# Controller.net
KiCad netlist of a schematic drawn in Altium Designer
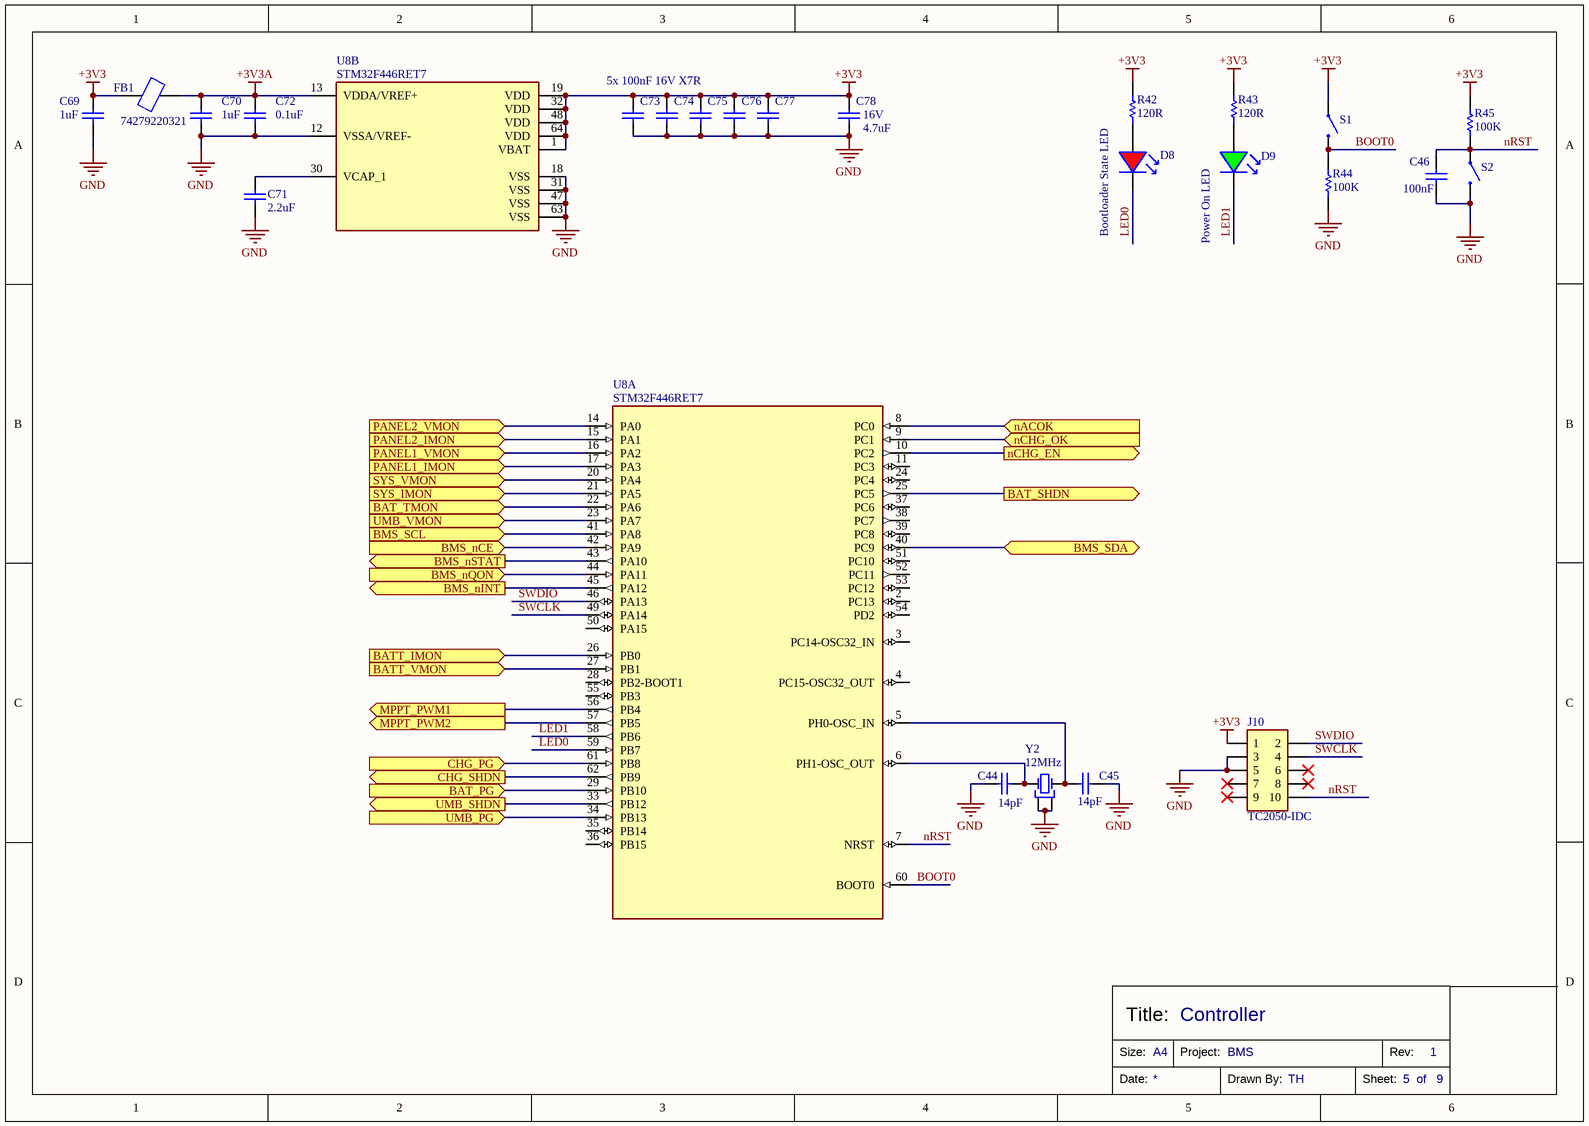
[diagram p0: Controller.SchDoc]

(export (version "E")
  (design (tool "Eeschema 10.0.6"))
  (components
    (comp (ref "C44")
      (value "GJM1555C1H140FB01D")
      (footprint "CAPC0402X020")
      (description "14 pF ±1% 50V Ceramic Capacitor C0G, NP0 0402 (1005 Metric)")
      (fields
        (field (name "TOLERANCE") "1%")
        (field (name "DISTRIBUTOR PART NUMBER") "2266-GJM1555C1H140FB01DTR-ND")
        (field (name "CAPACITANCE") "14pF")
      )
      (libsource (lib "Ahristi_Library") (part "CAPC0402"))
    )
    (comp (ref "C45")
      (value "GJM1555C1H140FB01D")
      (footprint "CAPC0402X020")
      (description "14 pF ±1% 50V Ceramic Capacitor C0G, NP0 0402 (1005 Metric)")
      (fields
        (field (name "TOLERANCE") "1%")
        (field (name "DISTRIBUTOR PART NUMBER") "2266-GJM1555C1H140FB01DTR-ND")
        (field (name "CAPACITANCE") "14pF")
      )
      (libsource (lib "Ahristi_Library") (part "CAPC0402"))
    )
    (comp (ref "C46")
      (value "CL10B104KO8NNNC")
      (footprint "CAPC0603X040")
      (description "0.1 µF ±10% 16V Ceramic Capacitor X7R 0603 (1608 Metric)")
      (fields
        (field (name "TOLERANCE") "10%")
        (field (name "DISTRIBUTOR PART NUMBER") "1276-1005-1-ND")
        (field (name "CAPACITANCE") "100nF")
      )
      (libsource (lib "Ahristi_Library") (part "CAPC0603"))
    )
    (comp (ref "C69")
      (value "CL10B105KO8NNNC")
      (footprint "CAPC0603X040")
      (description "1 µF ±10% 16V Ceramic Capacitor X7R 0603 (1608 Metric)")
      (fields
        (field (name "TOLERANCE") "10%")
        (field (name "DISTRIBUTOR PART NUMBER") "1276-1019-1-ND")
        (field (name "CAPACITANCE") "1uF")
      )
      (libsource (lib "Ahristi_Library") (part "CAPC0603"))
    )
    (comp (ref "C70")
      (value "CL10B105KO8NNNC")
      (footprint "CAPC0603X040")
      (description "1 µF ±10% 16V Ceramic Capacitor X7R 0603 (1608 Metric)")
      (fields
        (field (name "TOLERANCE") "10%")
        (field (name "DISTRIBUTOR PART NUMBER") "1276-1019-1-ND")
        (field (name "CAPACITANCE") "1uF")
      )
      (libsource (lib "Ahristi_Library") (part "CAPC0603"))
    )
    (comp (ref "C71")
      (value "CL21A225KBFNNNE")
      (footprint "CAPC0805X060")
      (description "2.2uF ±10% 25V Ceramic Capacitor X7R 0805 (2012 Metric)")
      (fields
        (field (name "DISTRIBUTOR PART NUMBER") "1276-6702-1-ND")
        (field (name "TOLERANCE") "10%")
        (field (name "CAPACITANCE") "2.2uF")
      )
      (libsource (lib "Ahristi_Library") (part "CL21A225KBFNNNE"))
    )
    (comp (ref "C72")
      (value "CL05B104KB5NNNC")
      (footprint "CAPC0402X020")
      (description "0.1 µF ±10% 50V Ceramic Capacitor X7R 0402 (1005 Metric)")
      (fields
        (field (name "TOLERANCE") "10%")
        (field (name "DISTRIBUTOR PART NUMBER") "1276-CL05B104KB5NNNCCT-ND")
        (field (name "CAPACITANCE") "0.1uF")
      )
      (libsource (lib "Ahristi_Library") (part "CL05B104KB5NNNC"))
    )
    (comp (ref "C73")
      (value "CL05B104KB5NNNC")
      (footprint "CAPC0402X020")
      (description "0.1 µF ±10% 50V Ceramic Capacitor X7R 0402 (1005 Metric)")
      (fields
        (field (name "TOLERANCE") "10%")
        (field (name "DISTRIBUTOR PART NUMBER") "1276-CL05B104KB5NNNCCT-ND")
      )
      (libsource (lib "Ahristi_Library") (part "CL05B104KB5NNNC"))
    )
    (comp (ref "C74")
      (value "CL05B104KB5NNNC")
      (footprint "CAPC0402X020")
      (description "0.1 µF ±10% 50V Ceramic Capacitor X7R 0402 (1005 Metric)")
      (fields
        (field (name "TOLERANCE") "10%")
        (field (name "DISTRIBUTOR PART NUMBER") "1276-CL05B104KB5NNNCCT-ND")
      )
      (libsource (lib "Ahristi_Library") (part "CL05B104KB5NNNC"))
    )
    (comp (ref "C75")
      (value "CL05B104KB5NNNC")
      (footprint "CAPC0402X020")
      (description "0.1 µF ±10% 50V Ceramic Capacitor X7R 0402 (1005 Metric)")
      (fields
        (field (name "TOLERANCE") "10%")
        (field (name "DISTRIBUTOR PART NUMBER") "1276-CL05B104KB5NNNCCT-ND")
      )
      (libsource (lib "Ahristi_Library") (part "CL05B104KB5NNNC"))
    )
    (comp (ref "C76")
      (value "CL05B104KB5NNNC")
      (footprint "CAPC0402X020")
      (description "0.1 µF ±10% 50V Ceramic Capacitor X7R 0402 (1005 Metric)")
      (fields
        (field (name "TOLERANCE") "10%")
        (field (name "DISTRIBUTOR PART NUMBER") "1276-CL05B104KB5NNNCCT-ND")
      )
      (libsource (lib "Ahristi_Library") (part "CL05B104KB5NNNC"))
    )
    (comp (ref "C77")
      (value "CL05B104KB5NNNC")
      (footprint "CAPC0402X020")
      (description "0.1 µF ±10% 50V Ceramic Capacitor X7R 0402 (1005 Metric)")
      (fields
        (field (name "TOLERANCE") "10%")
        (field (name "DISTRIBUTOR PART NUMBER") "1276-CL05B104KB5NNNCCT-ND")
      )
      (libsource (lib "Ahristi_Library") (part "CL05B104KB5NNNC"))
    )
    (comp (ref "C78")
      (value "CL21B475KOFNFNE")
      (footprint "CAPC0805X060")
      (description "4.7 µF ±10% 16V Ceramic Capacitor X7R 0805 (2012 Metric)")
      (fields
        (field (name "DISTRIBUTOR PART NUMBER") "1276-2970-1-ND")
        (field (name "TOLERANCE") "10%")
        (field (name "VOLTAGE RATING") "16V")
        (field (name "CAPACITANCE") "4.7uF")
      )
      (libsource (lib "Ahristi_Library") (part "CL21B475KOFNFNE"))
    )
    (comp (ref "D8")
      (value "LTST-C170EKT")
      (footprint "LEDR_0805")
      (description "Red 621nm LED Indication - Discrete 2V 0805 (2012 Metric)")
      (fields (field (name "DISTRIBUTOR PART NUMBER") "160-1178-1-ND"))
      (libsource (lib "Ahristi_Library") (part "LEDR0805"))
    )
    (comp (ref "D9")
      (value "LTST-C170GKT")
      (footprint "LEDG_0805")
      (description "Green 569nm LED Indication - Discrete 2.1V 0805 (2012 Metric)")
      (fields (field (name "DISTRIBUTOR PART NUMBER") "160-1179-1-ND"))
      (libsource (lib "Ahristi_Library") (part "LEDG0805"))
    )
    (comp (ref "FB1")
      (value "74279220321")
      (footprint "74279220321")
      (description "Ferrite Bead 320 Ohms @ 100 MHz 1 Ferrite Bead 0805 (2012 Metric) 2.5A 50mOhm")
      (fields (field (name "DISTRIBUTOR PART NUMBER") "732-6125-1-ND"))
      (libsource (lib "Ahristi_Library") (part "74279220321"))
    )
    (comp (ref "J10")
      (value "TC2050-IDC")
      (footprint "TC2050-IDC")
      (description "JTAG Pogo Programmer Pads")
      (libsource (lib "Ahristi_Library") (part "TC2050-IDC"))
    )
    (comp (ref "R42")
      (value "RMCF0805FT120R")
      (footprint "RESC0805")
      (description "120 Ohms ±1% 0.125W, 1/8W Chip Resistor 0805 (2012 Metric) Automotive AEC-Q200 Thick Film")
      (fields
        (field (name "TOLERANCE") "1%")
        (field (name "DISTRIBUTOR PART NUMBER") "738-RMCF0805FT120RCT-ND")
        (field (name "RESISTANCE") "120R")
      )
      (libsource (lib "Ahristi_Library") (part "RMCF0805FT120R"))
    )
    (comp (ref "R43")
      (value "RMCF0805FT120R")
      (footprint "RESC0805")
      (description "120 Ohms ±1% 0.125W, 1/8W Chip Resistor 0805 (2012 Metric) Automotive AEC-Q200 Thick Film")
      (fields
        (field (name "TOLERANCE") "1%")
        (field (name "DISTRIBUTOR PART NUMBER") "738-RMCF0805FT120RCT-ND")
        (field (name "RESISTANCE") "120R")
      )
      (libsource (lib "Ahristi_Library") (part "RMCF0805FT120R"))
    )
    (comp (ref "R44")
      (value "RMCF0603FT100K")
      (footprint "RESC0603")
      (description "100 kOhms ±1% 0.1W, 1/10W Chip Resistor 0603 (1608 Metric) Automotive AEC-Q200 Thick Film")
      (fields
        (field (name "TOLERANCE") "1%")
        (field (name "DISTRIBUTOR PART NUMBER") "RMCF0603FT100KCT-ND")
        (field (name "RESISTANCE") "100K")
      )
      (libsource (lib "Ahristi_Library") (part "RMCF0603FT100K"))
    )
    (comp (ref "R45")
      (value "RMCF0603FT100K")
      (footprint "RESC0603")
      (description "100 kOhms ±1% 0.1W, 1/10W Chip Resistor 0603 (1608 Metric) Automotive AEC-Q200 Thick Film")
      (fields
        (field (name "TOLERANCE") "1%")
        (field (name "DISTRIBUTOR PART NUMBER") "RMCF0603FT100KCT-ND")
        (field (name "RESISTANCE") "100K")
      )
      (libsource (lib "Ahristi_Library") (part "RMCF0603FT100K"))
    )
    (comp (ref "S1")
      (value "B3U-1000P")
      (footprint "B3U-1000P")
      (description "Tactile Switch SPST-NO Top Actuated Surface Mount")
      (fields (field (name "DISTRIBUTOR PART NUMBER") "SW1020CT-ND"))
      (libsource (lib "Ahristi_Library") (part "B3U-1000P"))
    )
    (comp (ref "S2")
      (value "B3U-1000P")
      (footprint "B3U-1000P")
      (description "Tactile Switch SPST-NO Top Actuated Surface Mount")
      (fields (field (name "DISTRIBUTOR PART NUMBER") "SW1020CT-ND"))
      (libsource (lib "Ahristi_Library") (part "B3U-1000P"))
    )
    (comp (ref "U8")
      (value "STM32F446RET7")
      (footprint "LQFP-64")
      (description "ARM® Cortex®-M4 STM32F4 Microcontroller IC 32-Bit 180MHz 512KB (512K x 8) FLASH 64-LQFP (10x10)")
      (fields
        (field (name "PART NUMBER") "STM32F446RET6")
        (field (name "DISTRIBUTOR PART NUMBER") "511-STM32F446RET7")
      )
      (libsource (lib "Ahristi_Library") (part "STM32F446RET7"))
    )
    (comp (ref "Y2")
      (value "830069882")
      (footprint "830069882")
      (description "Crystals 12.0 MHZ 18PF 20PPM 120OHM")
      (fields (field (name "FREQUENCY") "12MHz"))
      (libsource (lib "Ahristi_Library") (part "830069882"))
    )
  )
  (nets
    (net (code "1") (name "+3V3") (class "Default")
      (node (ref "C69") (pin "2") (pinfunction "2_2") (pintype "passive"))
      (node (ref "C73") (pin "2") (pinfunction "2_2") (pintype "passive"))
      (node (ref "C74") (pin "2") (pinfunction "2_2") (pintype "passive"))
      (node (ref "C75") (pin "2") (pinfunction "2_2") (pintype "passive"))
      (node (ref "C76") (pin "2") (pinfunction "2_2") (pintype "passive"))
      (node (ref "C77") (pin "2") (pinfunction "2_2") (pintype "passive"))
      (node (ref "C78") (pin "2") (pinfunction "2_2") (pintype "passive"))
      (node (ref "FB1") (pin "1") (pinfunction "1_1") (pintype "passive"))
      (node (ref "J10") (pin "1") (pinfunction "1_1") (pintype "passive"))
      (node (ref "R42") (pin "2") (pinfunction "2_2") (pintype "passive"))
      (node (ref "R43") (pin "2") (pinfunction "2_2") (pintype "passive"))
      (node (ref "R45") (pin "2") (pinfunction "2_2") (pintype "passive"))
      (node (ref "S1") (pin "1") (pinfunction "1_1") (pintype "passive"))
      (node (ref "U8") (pin "1") (pinfunction "VBAT_1") (pintype "power_in"))
      (node (ref "U8") (pin "19") (pinfunction "VDD_19") (pintype "power_in"))
      (node (ref "U8") (pin "32") (pinfunction "VDD_32") (pintype "power_in"))
      (node (ref "U8") (pin "48") (pinfunction "VDD_48") (pintype "power_in"))
      (node (ref "U8") (pin "64") (pinfunction "VDD_64") (pintype "power_in"))
    )
    (net (code "2") (name "+3V3A") (class "Default")
      (node (ref "C70") (pin "2") (pinfunction "2_2") (pintype "passive"))
      (node (ref "C72") (pin "2") (pinfunction "2_2") (pintype "passive"))
      (node (ref "FB1") (pin "2") (pinfunction "2_2") (pintype "passive"))
      (node (ref "U8") (pin "13") (pinfunction "VDDA/VREF+_13") (pintype "power_in"))
    )
    (net (code "3") (name "/BATT_IMON") (class "Default")
      (node (ref "U8") (pin "26") (pinfunction "PB0_26") (pintype "bidirectional"))
    )
    (net (code "4") (name "/BATT_VMON") (class "Default")
      (node (ref "U8") (pin "27") (pinfunction "PB1_27") (pintype "bidirectional"))
    )
    (net (code "5") (name "/BAT_PG") (class "Default")
      (node (ref "U8") (pin "29") (pinfunction "PB10_29") (pintype "bidirectional"))
    )
    (net (code "6") (name "/BAT_SHDN") (class "Default")
      (node (ref "U8") (pin "25") (pinfunction "PC5_25") (pintype "bidirectional"))
    )
    (net (code "7") (name "/BAT_TMON") (class "Default")
      (node (ref "U8") (pin "22") (pinfunction "PA6_22") (pintype "bidirectional"))
    )
    (net (code "8") (name "/BMS_SCL") (class "Default")
      (node (ref "U8") (pin "41") (pinfunction "PA8_41") (pintype "bidirectional"))
    )
    (net (code "9") (name "/BMS_SDA") (class "Default")
      (node (ref "U8") (pin "40") (pinfunction "PC9_40") (pintype "bidirectional"))
    )
    (net (code "10") (name "/BMS_nCE") (class "Default")
      (node (ref "U8") (pin "42") (pinfunction "PA9_42") (pintype "bidirectional"))
    )
    (net (code "11") (name "/BMS_nINT") (class "Default")
      (node (ref "U8") (pin "45") (pinfunction "PA12_45") (pintype "bidirectional"))
    )
    (net (code "12") (name "/BMS_nQON") (class "Default")
      (node (ref "U8") (pin "44") (pinfunction "PA11_44") (pintype "bidirectional"))
    )
    (net (code "13") (name "/BMS_nSTAT") (class "Default")
      (node (ref "U8") (pin "43") (pinfunction "PA10_43") (pintype "bidirectional"))
    )
    (net (code "14") (name "/BOOT0") (class "Default")
      (node (ref "R44") (pin "2") (pinfunction "2_2") (pintype "passive"))
      (node (ref "S1") (pin "2") (pinfunction "2_2") (pintype "passive"))
      (node (ref "U8") (pin "60") (pinfunction "BOOT0_60") (pintype "input"))
    )
    (net (code "15") (name "/CHG_PG") (class "Default")
      (node (ref "U8") (pin "61") (pinfunction "PB8_61") (pintype "bidirectional"))
    )
    (net (code "16") (name "/CHG_SHDN") (class "Default")
      (node (ref "U8") (pin "62") (pinfunction "PB9_62") (pintype "bidirectional"))
    )
    (net (code "17") (name "/LED0") (class "Default")
      (node (ref "D8") (pin "K") (pinfunction "K_K") (pintype "passive"))
      (node (ref "U8") (pin "59") (pinfunction "PB7_59") (pintype "bidirectional"))
    )
    (net (code "18") (name "/LED1") (class "Default")
      (node (ref "D9") (pin "K") (pinfunction "K_K") (pintype "passive"))
      (node (ref "U8") (pin "58") (pinfunction "PB6_58") (pintype "bidirectional"))
    )
    (net (code "19") (name "/MPPT_PWM1") (class "Default")
      (node (ref "U8") (pin "56") (pinfunction "PB4_56") (pintype "output"))
    )
    (net (code "20") (name "/MPPT_PWM2") (class "Default")
      (node (ref "U8") (pin "57") (pinfunction "PB5_57") (pintype "output"))
    )
    (net (code "21") (name "/PANEL1_IMON") (class "Default")
      (node (ref "U8") (pin "17") (pinfunction "PA3_17") (pintype "input"))
    )
    (net (code "22") (name "/PANEL1_VMON") (class "Default")
      (node (ref "U8") (pin "16") (pinfunction "PA2_16") (pintype "input"))
    )
    (net (code "23") (name "/PANEL2_IMON") (class "Default")
      (node (ref "U8") (pin "15") (pinfunction "PA1_15") (pintype "input"))
    )
    (net (code "24") (name "/PANEL2_VMON") (class "Default")
      (node (ref "U8") (pin "14") (pinfunction "PA0_14") (pintype "input"))
    )
    (net (code "25") (name "/SWCLK") (class "Default")
      (node (ref "J10") (pin "4") (pinfunction "4_4") (pintype "passive"))
      (node (ref "U8") (pin "49") (pinfunction "PA14_49") (pintype "bidirectional"))
    )
    (net (code "26") (name "/SWDIO") (class "Default")
      (node (ref "J10") (pin "2") (pinfunction "2_2") (pintype "passive"))
      (node (ref "U8") (pin "46") (pinfunction "PA13_46") (pintype "bidirectional"))
    )
    (net (code "27") (name "/SYS_IMON") (class "Default")
      (node (ref "U8") (pin "21") (pinfunction "PA5_21") (pintype "input"))
    )
    (net (code "28") (name "/SYS_VMON") (class "Default")
      (node (ref "U8") (pin "20") (pinfunction "PA4_20") (pintype "input"))
    )
    (net (code "29") (name "/UMB_PG") (class "Default")
      (node (ref "U8") (pin "34") (pinfunction "PB13_34") (pintype "bidirectional"))
    )
    (net (code "30") (name "/UMB_SHDN") (class "Default")
      (node (ref "U8") (pin "33") (pinfunction "PB12_33") (pintype "bidirectional"))
    )
    (net (code "31") (name "/UMB_VMON") (class "Default")
      (node (ref "U8") (pin "23") (pinfunction "PA7_23") (pintype "bidirectional"))
    )
    (net (code "32") (name "/nACOK") (class "Default")
      (node (ref "U8") (pin "8") (pinfunction "PC0_8") (pintype "input"))
    )
    (net (code "33") (name "/nCHG_EN") (class "Default")
      (node (ref "U8") (pin "10") (pinfunction "PC2_10") (pintype "output"))
    )
    (net (code "34") (name "/nCHG_OK") (class "Default")
      (node (ref "U8") (pin "9") (pinfunction "PC1_9") (pintype "input"))
    )
    (net (code "35") (name "/nRST") (class "Default")
      (node (ref "C46") (pin "2") (pinfunction "2_2") (pintype "passive"))
      (node (ref "J10") (pin "10") (pinfunction "10_10") (pintype "passive"))
      (node (ref "R45") (pin "1") (pinfunction "1_1") (pintype "passive"))
      (node (ref "S2") (pin "1") (pinfunction "1_1") (pintype "passive"))
      (node (ref "U8") (pin "7") (pinfunction "NRST_7") (pintype "bidirectional"))
    )
    (net (code "36") (name "GND") (class "Default")
      (node (ref "C44") (pin "1") (pinfunction "1_1") (pintype "passive"))
      (node (ref "C45") (pin "1") (pinfunction "1_1") (pintype "passive"))
      (node (ref "C46") (pin "1") (pinfunction "1_1") (pintype "passive"))
      (node (ref "C69") (pin "1") (pinfunction "1_1") (pintype "passive"))
      (node (ref "C70") (pin "1") (pinfunction "1_1") (pintype "passive"))
      (node (ref "C71") (pin "1") (pinfunction "1_1") (pintype "passive"))
      (node (ref "C72") (pin "1") (pinfunction "1_1") (pintype "passive"))
      (node (ref "C73") (pin "1") (pinfunction "1_1") (pintype "passive"))
      (node (ref "C74") (pin "1") (pinfunction "1_1") (pintype "passive"))
      (node (ref "C75") (pin "1") (pinfunction "1_1") (pintype "passive"))
      (node (ref "C76") (pin "1") (pinfunction "1_1") (pintype "passive"))
      (node (ref "C77") (pin "1") (pinfunction "1_1") (pintype "passive"))
      (node (ref "C78") (pin "1") (pinfunction "1_1") (pintype "passive"))
      (node (ref "J10") (pin "3") (pinfunction "3_3") (pintype "passive"))
      (node (ref "J10") (pin "5") (pinfunction "5_5") (pintype "passive"))
      (node (ref "R44") (pin "1") (pinfunction "1_1") (pintype "passive"))
      (node (ref "S2") (pin "2") (pinfunction "2_2") (pintype "passive"))
      (node (ref "U8") (pin "12") (pinfunction "VSSA/VREF-_12") (pintype "power_in"))
      (node (ref "U8") (pin "18") (pinfunction "VSS_18") (pintype "power_in"))
      (node (ref "U8") (pin "31") (pinfunction "VSS_31") (pintype "power_in"))
      (node (ref "U8") (pin "47") (pinfunction "VSS_47") (pintype "power_in"))
      (node (ref "U8") (pin "63") (pinfunction "VSS_63") (pintype "power_in"))
      (node (ref "Y2") (pin "2") (pinfunction "OSC1_2") (pintype "passive"))
      (node (ref "Y2") (pin "4") (pinfunction "OSC1_4") (pintype "passive"))
    )
    (net (code "37") (name "Net-(D8-PadA)") (class "Default")
      (node (ref "D8") (pin "A") (pinfunction "A_A") (pintype "passive"))
      (node (ref "R42") (pin "1") (pinfunction "1_1") (pintype "passive"))
    )
    (net (code "38") (name "Net-(D9-PadA)") (class "Default")
      (node (ref "D9") (pin "A") (pinfunction "A_A") (pintype "passive"))
      (node (ref "R43") (pin "1") (pinfunction "1_1") (pintype "passive"))
    )
    (net (code "39") (name "Net-(U8A-PH0-OSC_IN)") (class "Default")
      (node (ref "C45") (pin "2") (pinfunction "2_2") (pintype "passive"))
      (node (ref "U8") (pin "5") (pinfunction "PH0-OSC_IN_5") (pintype "bidirectional"))
      (node (ref "Y2") (pin "3") (pinfunction "OSC2_3") (pintype "passive"))
    )
    (net (code "40") (name "Net-(U8A-PH1-OSC_OUT)") (class "Default")
      (node (ref "C44") (pin "2") (pinfunction "2_2") (pintype "passive"))
      (node (ref "U8") (pin "6") (pinfunction "PH1-OSC_OUT_6") (pintype "bidirectional"))
      (node (ref "Y2") (pin "1") (pinfunction "OSC1_1") (pintype "passive"))
    )
    (net (code "41") (name "Net-(U8B-VCAP_1)") (class "Default")
      (node (ref "C71") (pin "2") (pinfunction "2_2") (pintype "passive"))
      (node (ref "U8") (pin "30") (pinfunction "VCAP_1_30") (pintype "power_in"))
    )
    (net (code "42") (name "unconnected-(J10-Pad6)") (class "Default")
      (node (ref "J10") (pin "6") (pinfunction "6_6") (pintype "passive+no_connect"))
    )
    (net (code "43") (name "unconnected-(J10-Pad7)") (class "Default")
      (node (ref "J10") (pin "7") (pinfunction "7_7") (pintype "passive+no_connect"))
    )
    (net (code "44") (name "unconnected-(J10-Pad8)") (class "Default")
      (node (ref "J10") (pin "8") (pinfunction "8_8") (pintype "passive+no_connect"))
    )
    (net (code "45") (name "unconnected-(J10-Pad9)") (class "Default")
      (node (ref "J10") (pin "9") (pinfunction "9_9") (pintype "passive+no_connect"))
    )
    (net (code "46") (name "unconnected-(U8A-PA15-Pad50)") (class "Default")
      (node (ref "U8") (pin "50") (pinfunction "PA15_50") (pintype "bidirectional"))
    )
    (net (code "47") (name "unconnected-(U8A-PB2-BOOT1-Pad28)") (class "Default")
      (node (ref "U8") (pin "28") (pinfunction "PB2-BOOT1_28") (pintype "bidirectional"))
    )
    (net (code "48") (name "unconnected-(U8A-PB3-Pad55)") (class "Default")
      (node (ref "U8") (pin "55") (pinfunction "PB3_55") (pintype "bidirectional"))
    )
    (net (code "49") (name "unconnected-(U8A-PB14-Pad35)") (class "Default")
      (node (ref "U8") (pin "35") (pinfunction "PB14_35") (pintype "bidirectional"))
    )
    (net (code "50") (name "unconnected-(U8A-PB15-Pad36)") (class "Default")
      (node (ref "U8") (pin "36") (pinfunction "PB15_36") (pintype "bidirectional"))
    )
    (net (code "51") (name "unconnected-(U8A-PC3-Pad11)") (class "Default")
      (node (ref "U8") (pin "11") (pinfunction "PC3_11") (pintype "bidirectional"))
    )
    (net (code "52") (name "unconnected-(U8A-PC4-Pad24)") (class "Default")
      (node (ref "U8") (pin "24") (pinfunction "PC4_24") (pintype "bidirectional"))
    )
    (net (code "53") (name "unconnected-(U8A-PC6-Pad37)") (class "Default")
      (node (ref "U8") (pin "37") (pinfunction "PC6_37") (pintype "output"))
    )
    (net (code "54") (name "unconnected-(U8A-PC7-Pad38)") (class "Default")
      (node (ref "U8") (pin "38") (pinfunction "PC7_38") (pintype "input"))
    )
    (net (code "55") (name "unconnected-(U8A-PC8-Pad39)") (class "Default")
      (node (ref "U8") (pin "39") (pinfunction "PC8_39") (pintype "bidirectional"))
    )
    (net (code "56") (name "unconnected-(U8A-PC10-Pad51)") (class "Default")
      (node (ref "U8") (pin "51") (pinfunction "PC10_51") (pintype "bidirectional"))
    )
    (net (code "57") (name "unconnected-(U8A-PC11-Pad52)") (class "Default")
      (node (ref "U8") (pin "52") (pinfunction "PC11_52") (pintype "output"))
    )
    (net (code "58") (name "unconnected-(U8A-PC12-Pad53)") (class "Default")
      (node (ref "U8") (pin "53") (pinfunction "PC12_53") (pintype "input"))
    )
    (net (code "59") (name "unconnected-(U8A-PC13-Pad2)") (class "Default")
      (node (ref "U8") (pin "2") (pinfunction "PC13_2") (pintype "bidirectional"))
    )
    (net (code "60") (name "unconnected-(U8A-PC14-OSC32_IN-Pad3)") (class "Default")
      (node (ref "U8") (pin "3") (pinfunction "PC14-OSC32_IN_3") (pintype "bidirectional"))
    )
    (net (code "61") (name "unconnected-(U8A-PC15-OSC32_OUT-Pad4)") (class "Default")
      (node (ref "U8") (pin "4") (pinfunction "PC15-OSC32_OUT_4") (pintype "bidirectional"))
    )
    (net (code "62") (name "unconnected-(U8A-PD2-Pad54)") (class "Default")
      (node (ref "U8") (pin "54") (pinfunction "PD2_54") (pintype "bidirectional"))
    )
  )
)
